# 20x20_adapter_rush_v4_m2.net
KiCad netlist of a schematic drawn in EAGLE
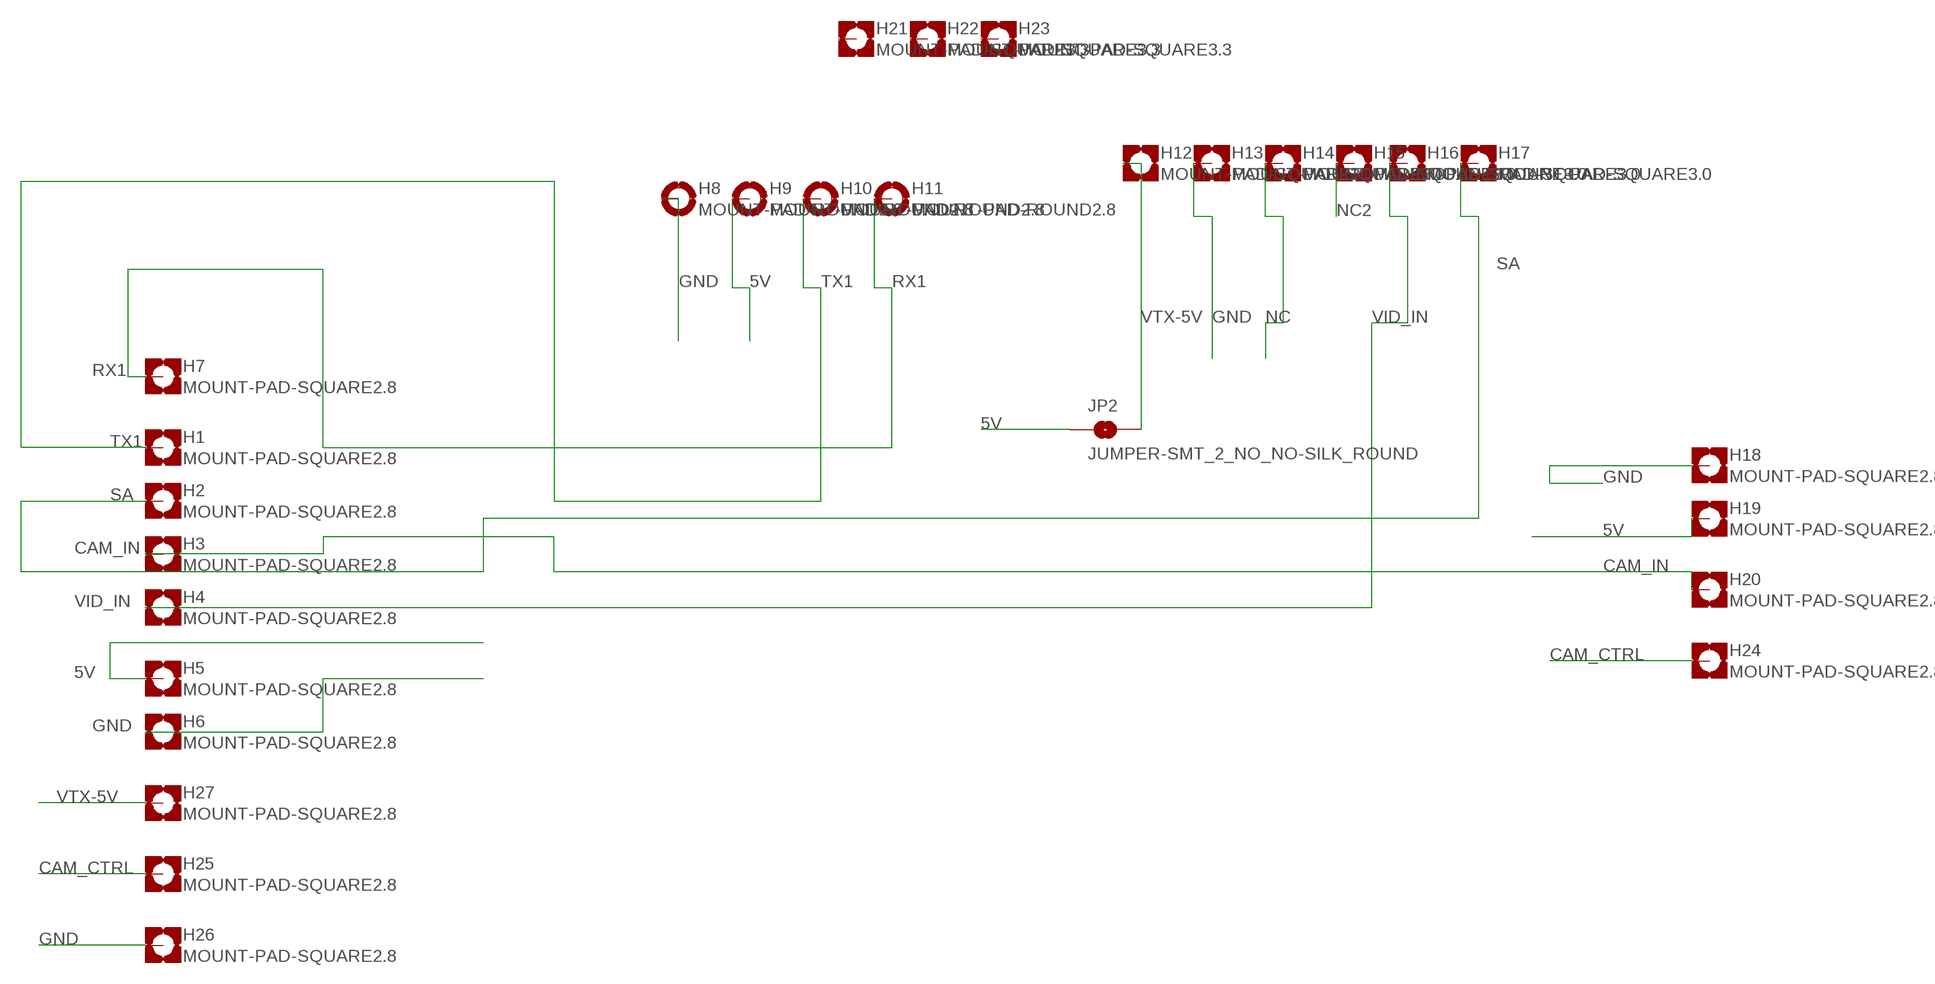
[diagram p0: schematic, sheet 1]

(export (version "E")
  (design (tool "Eeschema 10.0.6"))
  (components
    (comp (ref "H1")
      (value "MOUNT-PAD-SQUARE2.8")
      (footprint "eagle-import:2,8-PAD-SQUARE")
      (libsource (lib "eagle-import") (part "MOUNT-PAD-SQUARE2.8"))
    )
    (comp (ref "H2")
      (value "MOUNT-PAD-SQUARE2.8")
      (footprint "eagle-import:2,8-PAD-SQUARE")
      (libsource (lib "eagle-import") (part "MOUNT-PAD-SQUARE2.8"))
    )
    (comp (ref "H3")
      (value "MOUNT-PAD-SQUARE2.8")
      (footprint "eagle-import:2,8-PAD-SQUARE")
      (libsource (lib "eagle-import") (part "MOUNT-PAD-SQUARE2.8"))
    )
    (comp (ref "H4")
      (value "MOUNT-PAD-SQUARE2.8")
      (footprint "eagle-import:2,8-PAD-SQUARE")
      (libsource (lib "eagle-import") (part "MOUNT-PAD-SQUARE2.8"))
    )
    (comp (ref "H5")
      (value "MOUNT-PAD-SQUARE2.8")
      (footprint "eagle-import:2,8-PAD-SQUARE")
      (libsource (lib "eagle-import") (part "MOUNT-PAD-SQUARE2.8"))
    )
    (comp (ref "H6")
      (value "MOUNT-PAD-SQUARE2.8")
      (footprint "eagle-import:2,8-PAD-SQUARE")
      (libsource (lib "eagle-import") (part "MOUNT-PAD-SQUARE2.8"))
    )
    (comp (ref "H7")
      (value "MOUNT-PAD-SQUARE2.8")
      (footprint "eagle-import:2,8-PAD-SQUARE")
      (libsource (lib "eagle-import") (part "MOUNT-PAD-SQUARE2.8"))
    )
    (comp (ref "H8")
      (value "MOUNT-PAD-ROUND2.8")
      (footprint "eagle-import:1,0-PAD")
      (libsource (lib "eagle-import") (part "MOUNT-PAD-ROUND2.8"))
    )
    (comp (ref "H9")
      (value "MOUNT-PAD-ROUND2.8")
      (footprint "eagle-import:1,0-PAD")
      (libsource (lib "eagle-import") (part "MOUNT-PAD-ROUND2.8"))
    )
    (comp (ref "H10")
      (value "MOUNT-PAD-ROUND2.8")
      (footprint "eagle-import:1,0-PAD")
      (libsource (lib "eagle-import") (part "MOUNT-PAD-ROUND2.8"))
    )
    (comp (ref "H11")
      (value "MOUNT-PAD-ROUND2.8")
      (footprint "eagle-import:1,0-PAD")
      (libsource (lib "eagle-import") (part "MOUNT-PAD-ROUND2.8"))
    )
    (comp (ref "H12")
      (value "MOUNT-PAD-SQUARE3.0")
      (footprint "eagle-import:1,5-PAD-SQUARE")
      (libsource (lib "eagle-import") (part "MOUNT-PAD-SQUARE3.0"))
    )
    (comp (ref "H13")
      (value "MOUNT-PAD-SQUARE3.0")
      (footprint "eagle-import:1,5-PAD-SQUARE")
      (libsource (lib "eagle-import") (part "MOUNT-PAD-SQUARE3.0"))
    )
    (comp (ref "H14")
      (value "MOUNT-PAD-SQUARE3.0")
      (footprint "eagle-import:1,5-PAD-SQUARE")
      (libsource (lib "eagle-import") (part "MOUNT-PAD-SQUARE3.0"))
    )
    (comp (ref "H15")
      (value "MOUNT-PAD-SQUARE3.0")
      (footprint "eagle-import:1,5-PAD-SQUARE")
      (libsource (lib "eagle-import") (part "MOUNT-PAD-SQUARE3.0"))
    )
    (comp (ref "H16")
      (value "MOUNT-PAD-SQUARE3.0")
      (footprint "eagle-import:1,5-PAD-SQUARE")
      (libsource (lib "eagle-import") (part "MOUNT-PAD-SQUARE3.0"))
    )
    (comp (ref "H17")
      (value "MOUNT-PAD-SQUARE3.0")
      (footprint "eagle-import:1,5-PAD-SQUARE")
      (libsource (lib "eagle-import") (part "MOUNT-PAD-SQUARE3.0"))
    )
    (comp (ref "H18")
      (value "MOUNT-PAD-SQUARE2.8")
      (footprint "eagle-import:2,8-PAD-SQUARE")
      (libsource (lib "eagle-import") (part "MOUNT-PAD-SQUARE2.8"))
    )
    (comp (ref "H19")
      (value "MOUNT-PAD-SQUARE2.8")
      (footprint "eagle-import:2,8-PAD-SQUARE")
      (libsource (lib "eagle-import") (part "MOUNT-PAD-SQUARE2.8"))
    )
    (comp (ref "H20")
      (value "MOUNT-PAD-SQUARE2.8")
      (footprint "eagle-import:2,8-PAD-SQUARE")
      (libsource (lib "eagle-import") (part "MOUNT-PAD-SQUARE2.8"))
    )
    (comp (ref "H21")
      (value "MOUNT-PAD-SQUARE3.3")
      (footprint "eagle-import:3,3-PAD-SQUARE")
      (libsource (lib "eagle-import") (part "MOUNT-PAD-SQUARE3.3"))
    )
    (comp (ref "H22")
      (value "MOUNT-PAD-SQUARE3.3")
      (footprint "eagle-import:3,3-PAD-SQUARE")
      (libsource (lib "eagle-import") (part "MOUNT-PAD-SQUARE3.3"))
    )
    (comp (ref "H23")
      (value "MOUNT-PAD-SQUARE3.3")
      (footprint "eagle-import:3,3-PAD-SQUARE")
      (libsource (lib "eagle-import") (part "MOUNT-PAD-SQUARE3.3"))
    )
    (comp (ref "H24")
      (value "MOUNT-PAD-SQUARE2.8")
      (footprint "eagle-import:2,8-PAD-SQUARE")
      (libsource (lib "eagle-import") (part "MOUNT-PAD-SQUARE2.8"))
    )
    (comp (ref "H25")
      (value "MOUNT-PAD-SQUARE2.8")
      (footprint "eagle-import:2,8-PAD-SQUARE")
      (libsource (lib "eagle-import") (part "MOUNT-PAD-SQUARE2.8"))
    )
    (comp (ref "H26")
      (value "MOUNT-PAD-SQUARE2.8")
      (footprint "eagle-import:2,8-PAD-SQUARE")
      (libsource (lib "eagle-import") (part "MOUNT-PAD-SQUARE2.8"))
    )
    (comp (ref "H27")
      (value "MOUNT-PAD-SQUARE2.8")
      (footprint "eagle-import:2,8-PAD-SQUARE")
      (libsource (lib "eagle-import") (part "MOUNT-PAD-SQUARE2.8"))
    )
    (comp (ref "JP2")
      (value "JUMPER-SMT_2_NO_NO-SILK_ROUND")
      (footprint "eagle-import:SMT-JUMPER_2_NO_NO-SILK_ROUND")
      (libsource (lib "eagle-import") (part "JUMPER-SMT_2_NO_NO-SILK_ROUND"))
    )
  )
  (nets
    (net (code "1") (name "/5V") (class "Default")
      (node (ref "H19") (pin "P$2") (pinfunction "MOUNT_P$2") (pintype "passive"))
      (node (ref "H5") (pin "P$2") (pinfunction "MOUNT_P$2") (pintype "passive"))
      (node (ref "H9") (pin "B1,0") (pinfunction "MOUNT_B1,0") (pintype "passive"))
      (node (ref "JP2") (pin "1") (pinfunction "1_1") (pintype "passive"))
    )
    (net (code "2") (name "/CAM_CTRL") (class "Default")
      (node (ref "H24") (pin "P$2") (pinfunction "MOUNT_P$2") (pintype "passive"))
      (node (ref "H25") (pin "P$2") (pinfunction "MOUNT_P$2") (pintype "passive"))
    )
    (net (code "3") (name "/CAM_IN") (class "Default")
      (node (ref "H20") (pin "P$2") (pinfunction "MOUNT_P$2") (pintype "passive"))
      (node (ref "H3") (pin "P$2") (pinfunction "MOUNT_P$2") (pintype "passive"))
    )
    (net (code "4") (name "/GND") (class "Default")
      (node (ref "H13") (pin "P$1") (pinfunction "MOUNT_P$1") (pintype "passive"))
      (node (ref "H18") (pin "P$2") (pinfunction "MOUNT_P$2") (pintype "passive"))
      (node (ref "H26") (pin "P$2") (pinfunction "MOUNT_P$2") (pintype "passive"))
      (node (ref "H6") (pin "P$2") (pinfunction "MOUNT_P$2") (pintype "passive"))
      (node (ref "H8") (pin "B1,0") (pinfunction "MOUNT_B1,0") (pintype "passive"))
    )
    (net (code "5") (name "/NC") (class "Default")
      (node (ref "H14") (pin "P$1") (pinfunction "MOUNT_P$1") (pintype "passive"))
    )
    (net (code "6") (name "/NC2") (class "Default")
      (node (ref "H15") (pin "P$1") (pinfunction "MOUNT_P$1") (pintype "passive"))
    )
    (net (code "7") (name "/RX1") (class "Default")
      (node (ref "H11") (pin "B1,0") (pinfunction "MOUNT_B1,0") (pintype "passive"))
      (node (ref "H7") (pin "P$2") (pinfunction "MOUNT_P$2") (pintype "passive"))
    )
    (net (code "8") (name "/SA") (class "Default")
      (node (ref "H17") (pin "P$1") (pinfunction "MOUNT_P$1") (pintype "passive"))
      (node (ref "H2") (pin "P$2") (pinfunction "MOUNT_P$2") (pintype "passive"))
    )
    (net (code "9") (name "/TX1") (class "Default")
      (node (ref "H1") (pin "P$2") (pinfunction "MOUNT_P$2") (pintype "passive"))
      (node (ref "H10") (pin "B1,0") (pinfunction "MOUNT_B1,0") (pintype "passive"))
    )
    (net (code "10") (name "/VID_IN") (class "Default")
      (node (ref "H16") (pin "P$1") (pinfunction "MOUNT_P$1") (pintype "passive"))
      (node (ref "H4") (pin "P$2") (pinfunction "MOUNT_P$2") (pintype "passive"))
    )
    (net (code "11") (name "/VTX-5V") (class "Default")
      (node (ref "H12") (pin "P$1") (pinfunction "MOUNT_P$1") (pintype "passive"))
      (node (ref "H27") (pin "P$2") (pinfunction "MOUNT_P$2") (pintype "passive"))
      (node (ref "JP2") (pin "2") (pinfunction "2_2") (pintype "passive"))
    )
    (net (code "12") (name "unconnected-(H21-MOUNT-PadP$1)") (class "Default")
      (node (ref "H21") (pin "P$1") (pinfunction "MOUNT_P$1") (pintype "passive"))
    )
    (net (code "13") (name "unconnected-(H22-MOUNT-PadP$1)") (class "Default")
      (node (ref "H22") (pin "P$1") (pinfunction "MOUNT_P$1") (pintype "passive"))
    )
    (net (code "14") (name "unconnected-(H23-MOUNT-PadP$1)") (class "Default")
      (node (ref "H23") (pin "P$1") (pinfunction "MOUNT_P$1") (pintype "passive"))
    )
  )
)
